# POWER.net
KiCad netlist of a schematic drawn in Altium Designer
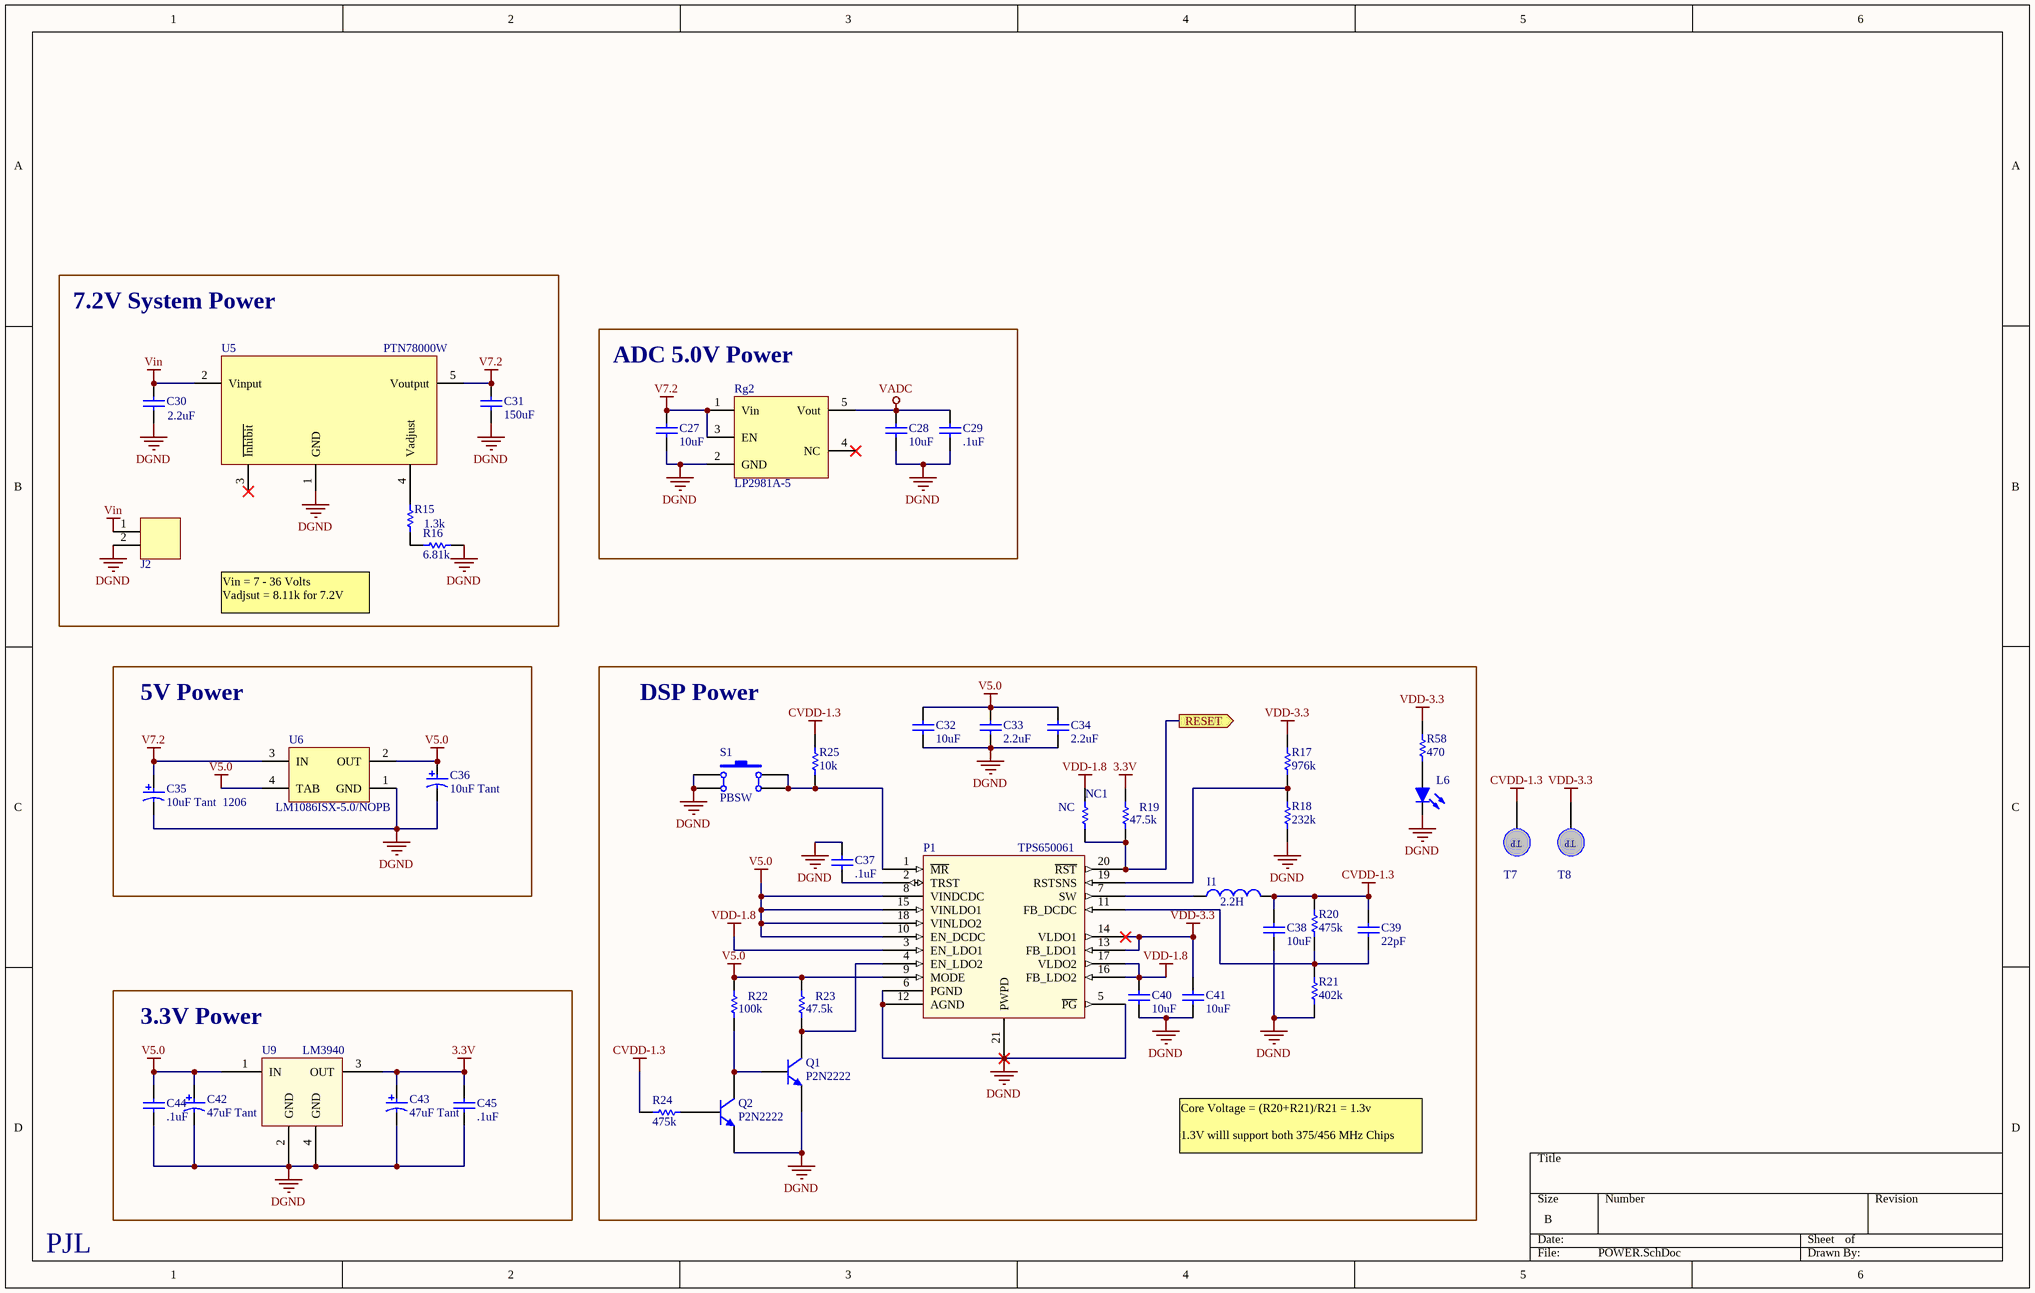
[diagram p0: POWER.SchDoc]

(export (version "E")
  (design (tool "Eeschema 10.0.6"))
  (components
    (comp (ref "C27")
      (value "10uF")
      (footprint "CAPC2012XL")
      (description "CAP CER 10UF 10V 10% X7R 0805")
      (fields
        (field (name "TOLERANCE") "±10%")
        (field (name "MANUFACTURER") "Murata Electronics North America")
      )
      (libsource (lib "SubLibrary") (part "CAP-CERAMIC-NP"))
    )
    (comp (ref "C28")
      (value "10uF")
      (footprint "CAPC2012XL")
      (description "CAP CER 10UF 10V 10% X7R 0805")
      (fields
        (field (name "TOLERANCE") "±10%")
        (field (name "MANUFACTURER") "Murata Electronics North America")
      )
      (libsource (lib "SubLibrary") (part "CAP-CERAMIC-NP"))
    )
    (comp (ref "C29")
      (value ".1uF")
      (footprint "CAPC1608XN")
      (description "CAP CER 0.1UF 10V 20% X7R 0603")
      (fields (field (name "MANUFACTURER PART NUMBER") "CX0603MRX7R6BB104") (field (name "TOLERANCE") "±20%"))
      (libsource (lib "Any") (part "CAP-CERAMIC-NP"))
    )
    (comp (ref "C30")
      (value "2.2uF")
      (footprint "CAPC2012XL")
      (description "Non Polarized Capacitor 2.2uF")
      (fields
        (field (name "MANUFACTURER") "TDK Corporation")
        (field (name "MANUFACTURER PART NUMBER") "C2012X5R1H225K")
      )
      (libsource (lib "MyLibraries") (part "Capacitor"))
    )
    (comp (ref "C31")
      (value "150uF")
      (footprint "PaulsAltiumLibrary:CAPPR2.5-6.3x11")
      (description "CAP ALUM 150UF 25V 20% RADIAL")
      (fields
        (field (name "MANUFACTURER") "Panasonic Electronic Components")
        (field (name "MANUFACTURER PART NUMBER") "EEU-FR1E151")
      )
      (libsource (lib "MyLibraries") (part "Capacitor"))
    )
    (comp (ref "C32")
      (value "10uF")
      (footprint "CAPC2012XL")
      (description "CAP CER 10UF 10V 10% X7R 0805")
      (fields
        (field (name "TOLERANCE") "±10%")
        (field (name "MANUFACTURER") "Murata Electronics North America")
      )
      (libsource (lib "SubLibrary") (part "CAP-CERAMIC-NP"))
    )
    (comp (ref "C33")
      (value "2.2uF")
      (footprint "CAPC1608XN")
      (description "CAP CER 2.2UF 10V 10% X5R 0603")
      (fields
        (field (name "TOLERANCE") "±10%")
        (field (name "MANUFACTURER") "Murata Electronics North America")
      )
      (libsource (lib "Any") (part "CAP-CERAMIC-NP"))
    )
    (comp (ref "C34")
      (value "2.2uF")
      (footprint "CAPC1608XN")
      (description "CAP CER 2.2UF 10V 10% X5R 0603")
      (fields
        (field (name "TOLERANCE") "±10%")
        (field (name "MANUFACTURER") "Murata Electronics North America")
      )
      (libsource (lib "Any") (part "CAP-CERAMIC-NP"))
    )
    (comp (ref "C35")
      (value "10uF Tant  1206")
      (footprint "CAPMP3216XN")
      (description "Capacitor, Tantalum, Polarized")
      (fields
        (field (name "MANUFACTURER") "Vishay Sprague")
        (field (name "MANUFACTURER PART NUMBER") "293D106X9016A2TE3")
      )
      (libsource (lib "Passives") (part "CAP-TANT"))
    )
    (comp (ref "C36")
      (value "10uF Tant")
      (footprint "CAPMP2012XL")
      (description "Capacitor, Tantalum, Polarized")
      (fields (field (name "MANUFACTURER") "AVX Corporation") (field (name "TOLERANCE") "±20%"))
      (libsource (lib "Passives") (part "CAP-TANT"))
    )
    (comp (ref "C37")
      (value ".1uF")
      (footprint "CAPC1608XN")
      (description "CAP CER 0.1UF 16V 10% X7R 0603")
      (fields
        (field (name "TOLERANCE") "±10%")
        (field (name "MANUFACTURER PART NUMBER") "GRM188R71C104KA01D")
      )
      (libsource (lib "Any") (part "CAP-CERAMIC-NP"))
    )
    (comp (ref "C38")
      (value "10uF")
      (footprint "CAPC2012XL")
      (description "CAP CER 10UF 10V 10% X7R 0805")
      (fields
        (field (name "TOLERANCE") "±10%")
        (field (name "MANUFACTURER") "Murata Electronics North America")
      )
      (libsource (lib "SubLibrary") (part "CAP-CERAMIC-NP"))
    )
    (comp (ref "C39")
      (value "22pF")
      (footprint "CAPC1608XN")
      (description "CAP CER 22PF 50V 5% NP0 0603")
      (fields
        (field (name "TOLERANCE") "±5%")
        (field (name "MANUFACTURER") "Murata Electronics North America")
      )
      (libsource (lib "Any") (part "CAP-CERAMIC-NP"))
    )
    (comp (ref "C40")
      (value "10uF")
      (footprint "CAPC2012XL")
      (description "CAP CER 10UF 10V 10% X7R 0805")
      (fields
        (field (name "TOLERANCE") "±10%")
        (field (name "MANUFACTURER") "Murata Electronics North America")
      )
      (libsource (lib "SubLibrary") (part "CAP-CERAMIC-NP"))
    )
    (comp (ref "C41")
      (value "10uF")
      (footprint "CAPC2012XL")
      (description "CAP CER 10UF 10V 10% X7R 0805")
      (fields
        (field (name "TOLERANCE") "±10%")
        (field (name "MANUFACTURER") "Murata Electronics North America")
      )
      (libsource (lib "SubLibrary") (part "CAP-CERAMIC-NP"))
    )
    (comp (ref "C42")
      (value "47uF Tant")
      (footprint "CAPMP2012XL")
      (description "Capacitor, Tantalum, Polarized")
      (fields
        (field (name "MANUFACTURER PART NUMBER") "TLJR476M010R3200")
        (field (name "MANUFACTURER") "AVX Corporation")
      )
      (libsource (lib "Passives") (part "CAP-TANT"))
    )
    (comp (ref "C43")
      (value "47uF Tant")
      (footprint "CAPMP2012XL")
      (description "Capacitor, Tantalum, Polarized")
      (fields
        (field (name "MANUFACTURER PART NUMBER") "TLJR476M010R3200")
        (field (name "MANUFACTURER") "AVX Corporation")
      )
      (libsource (lib "Passives") (part "CAP-TANT"))
    )
    (comp (ref "C44")
      (value ".1uF")
      (footprint "CAPC1608XN")
      (description "CAP CER 0.1UF 10V 20% X7R 0603")
      (fields (field (name "MANUFACTURER PART NUMBER") "CX0603MRX7R6BB104") (field (name "TOLERANCE") "±20%"))
      (libsource (lib "Any") (part "CAP-CERAMIC-NP"))
    )
    (comp (ref "C45")
      (value ".1uF")
      (footprint "CAPC1608XN")
      (description "CAP CER 0.1UF 10V 20% X7R 0603")
      (fields (field (name "MANUFACTURER PART NUMBER") "CX0603MRX7R6BB104") (field (name "TOLERANCE") "±20%"))
      (libsource (lib "Any") (part "CAP-CERAMIC-NP"))
    )
    (comp (ref "I1")
      (value "2.2H")
      (footprint "LPS3015")
      (fields
        (field (name "MANUFACTURER") "Coilcraft")
        (field (name "MANUFACTURER PART NUMBER") "LPS3015-222ML")
      )
      (libsource (lib "PaulsAltiumLibrary") (part "VLC5045"))
    )
    (comp (ref "J2")
      (value "2-pin Horz Sherlock")
      (footprint "MOLEX-HDR-1X2-SHERLOCK-HORZ")
      (fields
        (field (name "MANUFACTURER PART NUMBER") "0353630260")
        (field (name "MANUFACTURER") "Molex Inc")
      )
      (libsource (lib "Connectors") (part "MOLEX-HDR-1x2-SHERLOCK_RA"))
    )
    (comp (ref "L6")
      (value "LED-GREEN")
      (footprint "LED0805-GREEN")
      (description "LED GREEN CLEAR THIN 0805 SMD")
      (fields (field (name "MANUFACTURER PART NUMBER") "LTST-C171GKT"))
      (libsource (lib "Hydrophone") (part "LED-GREEN"))
    )
    (comp (ref "NC1")
      (value "NC")
      (footprint "RESC1608XN")
      (description "Resistor Chip")
      (libsource (lib "Any") (part "RES-CHIP"))
    )
    (comp (ref "P1")
      (value "TPS650061")
      (footprint "Hydrophone:QFN4-20N")
      (description "IC CONV STP-DWN 2.25MHZ DL 20QFN")
      (fields
        (field (name "MANUFACTURER") "Texas Instruments")
        (field (name "MANUFACTURER PART NUMBER") "TPS650061RUKT")
      )
      (libsource (lib "Hydrophone") (part "TPS650061"))
    )
    (comp (ref "Q1")
      (value "P2N2222")
      (footprint "PaulsAltiumLibrary:TO-92A")
      (description "TRANS GP SS NPN LP 40V TO92")
      (fields
        (field (name "MANUFACTURER PART NUMBER") "P2N2222AG")
        (field (name "MANUFACTURER") "ON Semiconductor")
      )
      (libsource (lib "Hydrophone") (part "P2N2222"))
    )
    (comp (ref "Q2")
      (value "P2N2222")
      (footprint "PaulsAltiumLibrary:TO-92A")
      (description "TRANS GP SS NPN LP 40V TO92")
      (fields
        (field (name "MANUFACTURER PART NUMBER") "P2N2222AG")
        (field (name "MANUFACTURER") "ON Semiconductor")
      )
      (libsource (lib "Hydrophone") (part "P2N2222"))
    )
    (comp (ref "R15")
      (value "1.3k")
      (footprint "RESC1608XL")
      (description "1.3k Ohm Resistor")
      (fields (field (name "TOLERANCE") "±0.5%") (field (name "MANUFACTURER PART NUMBER") "RT0603DRD071K3L"))
      (libsource (lib "MyLibraries") (part "Resistor"))
    )
    (comp (ref "R16")
      (value "6.81k")
      (footprint "RESC1608XL")
      (description "Resistor 6.81k")
      (fields (field (name "TOLERANCE") "±0.5%") (field (name "MANUFACTURER") "Yageo"))
      (libsource (lib "MyLibraries") (part "Resistor"))
    )
    (comp (ref "R17")
      (value "976k")
      (footprint "RESC1608XL")
      (description "Resistor Chip")
      (fields (field (name "MANUFACTURER PART NUMBER") "RC0603FR-07976KL") (field (name "TOLERANCE") "±1%"))
      (libsource (lib "Any") (part "RES-CHIP"))
    )
    (comp (ref "R18")
      (value "232k")
      (footprint "RESC1608XL")
      (description "Resistor Chip")
      (fields (field (name "TOLERANCE") "±1%") (field (name "MANUFACTURER PART NUMBER") "CRCW0603232KFKEA"))
      (libsource (lib "Any") (part "RES-CHIP"))
    )
    (comp (ref "R19")
      (value "47.5k")
      (footprint "RESC1608XN")
      (description "RES 47.5K OHM 1/16W 1% 0603")
      (fields (field (name "MANUFACTURER") "TE Connectivity"))
      (libsource (lib "Any") (part "RES-CHIP"))
    )
    (comp (ref "R20")
      (value "475k")
      (footprint "RESC1608XL")
      (description "Resistor Chip")
      (fields (field (name "TOLERANCE") "±1%") (field (name "MANUFACTURER") "Yageo"))
      (libsource (lib "Any") (part "RES-CHIP"))
    )
    (comp (ref "R21")
      (value "402k")
      (footprint "RESC1608XL")
      (description "RES 402K OHM 1/10W 1% 0603 SMD")
      (fields (field (name "MANUFACTURER") "Yageo") (field (name "TOLERANCE") "±1%"))
      (libsource (lib "Any") (part "RES-CHIP"))
    )
    (comp (ref "R22")
      (value "100k")
      (footprint "RESC1608XL")
      (description "RES 100K OHM 1/10W 1% 0603 SMD")
      (fields
        (field (name "MANUFACTURER PART NUMBER") "RC0603FR-07100KL")
        (field (name "MANUFACTURER") "Yageo")
      )
      (libsource (lib "Any") (part "RES-CHIP"))
    )
    (comp (ref "R23")
      (value "47.5k")
      (footprint "RESC1608XN")
      (description "RES 47.5K OHM 1/16W 1% 0603")
      (fields (field (name "MANUFACTURER") "TE Connectivity"))
      (libsource (lib "Any") (part "RES-CHIP"))
    )
    (comp (ref "R24")
      (value "475k")
      (footprint "RESC1608XL")
      (description "Resistor Chip")
      (fields (field (name "TOLERANCE") "±1%") (field (name "MANUFACTURER") "Yageo"))
      (libsource (lib "Any") (part "RES-CHIP"))
    )
    (comp (ref "R25")
      (value "10k")
      (footprint "RESC1608XL")
      (description "RES 10K OHM 1/10W 5% 0603 SMD")
      (fields (field (name "MANUFACTURER") "Yageo"))
      (libsource (lib "SubLibrary") (part "RES-CHIP"))
    )
    (comp (ref "R58")
      (value "470")
      (footprint "RESC1608XN")
      (description "RES 470 OHM .25W 5% 0603 SMD")
      (fields
        (field (name "MANUFACTURER") "Vishay Dale")
        (field (name "MANUFACTURER PART NUMBER") "CRCW0603470RJNEAHP")
      )
      (libsource (lib "SubLibrary") (part "RES-CHIP"))
    )
    (comp (ref "Rg2")
      (value "LP2981A-5")
      (footprint "TI-SOT-23_5N")
      (description "100mA 5v LDO - 0.75% accuracy")
      (fields
        (field (name "MANUFACTURER") "Texas Instruments")
        (field (name "MANUFACTURER PART NUMBER") "LP2981A-50DBVT")
      )
      (libsource (lib "SubLibrary") (part "LP2981A"))
    )
    (comp (ref "S1")
      (value "PBSW")
      (footprint "Hydrophone:PBSW")
      (description "SWITCH TACTILE SPST-NO 0.05A 12V")
      (fields
        (field (name "MANUFACTURER") "Panasonic Electronic Components")
        (field (name "PUBLISHER") "Altium Limited")
      )
      (libsource (lib "Hydrophone") (part "SW-PB"))
    )
    (comp (ref "T7")
      (value "TEST MINI")
      (footprint "TEST-POINT - 5015")
      (description "PC TEST POINT MINIATURE SMT")
      (fields
        (field (name "MANUFACTURER") "Keystone Electronics")
        (field (name "MANUFACTURER PART NUMBER") "5015")
      )
      (libsource (lib "Any") (part "TEST-POINT"))
    )
    (comp (ref "T8")
      (value "TEST MINI")
      (footprint "TEST-POINT - 5015")
      (description "PC TEST POINT MINIATURE SMT")
      (fields
        (field (name "MANUFACTURER") "Keystone Electronics")
        (field (name "MANUFACTURER PART NUMBER") "5015")
      )
      (libsource (lib "Any") (part "TEST-POINT"))
    )
    (comp (ref "U5")
      (value "PTN78000W")
      (footprint "TI-EUS - 3d")
      (description "1.5A, 7-36V Input, Variable Switching Voltage Regulator")
      (fields
        (field (name "MANUFACTURER PART NUMBER") "PTN78000WAH")
        (field (name "ORDER PART NUMBER") "296-20506-ND")
      )
      (libsource (lib "Power") (part "PTN78000W"))
    )
    (comp (ref "U6")
      (value "LM1086ISX-5.0/NOPB")
      (footprint "Hydrophone:TO263")
      (description "IC REG LDO 5V 1.5A TO-263")
      (fields (field (name "MANUFACTURER") "National Semiconductor"))
      (libsource (lib "NSC LDO") (part "LM1086ISX-5.0/NOPB"))
    )
    (comp (ref "U9")
      (value "LM3940")
      (footprint "SOT230P700X155-4N")
      (description "IC REG LDO 3.3V 1A SOT-223")
      (fields (field (name "MANUFACTURER") "National Semiconductor"))
      (libsource (lib "MyLibraries") (part "LM3940"))
    )
  )
  (nets
    (net (code "1") (name "/RESET") (class "Default")
      (node (ref "NC1") (pin "1") (pinfunction "1_1") (pintype "passive"))
      (node (ref "P1") (pin "20") (pinfunction "~{RST}_20") (pintype "output"))
      (node (ref "R19") (pin "1") (pinfunction "1_1") (pintype "passive"))
    )
    (net (code "2") (name "3.3V") (class "Default")
      (node (ref "C43") (pin "1") (pinfunction "1_1") (pintype "passive"))
      (node (ref "C45") (pin "2") (pinfunction "2_2") (pintype "passive"))
      (node (ref "R19") (pin "2") (pinfunction "2_2") (pintype "passive"))
      (node (ref "U9") (pin "3") (pinfunction "OUT_3") (pintype "power_in"))
    )
    (net (code "3") (name "CVDD-1.3") (class "Default")
      (node (ref "C38") (pin "2") (pinfunction "2_2") (pintype "passive"))
      (node (ref "C39") (pin "2") (pinfunction "2_2") (pintype "passive"))
      (node (ref "I1") (pin "2") (pinfunction "2_2") (pintype "passive"))
      (node (ref "R20") (pin "2") (pinfunction "2_2") (pintype "passive"))
      (node (ref "R24") (pin "2") (pinfunction "2_2") (pintype "passive"))
      (node (ref "R25") (pin "2") (pinfunction "2_2") (pintype "passive"))
      (node (ref "T7") (pin "1") (pinfunction "1_1") (pintype "passive"))
    )
    (net (code "4") (name "DGND") (class "Default")
      (node (ref "C27") (pin "1") (pinfunction "1_1") (pintype "passive"))
      (node (ref "C28") (pin "1") (pinfunction "1_1") (pintype "passive"))
      (node (ref "C29") (pin "1") (pinfunction "1_1") (pintype "passive"))
      (node (ref "C30") (pin "1") (pinfunction "1_1") (pintype "passive"))
      (node (ref "C31") (pin "2") (pinfunction "2_2") (pintype "passive"))
      (node (ref "C32") (pin "1") (pinfunction "1_1") (pintype "passive"))
      (node (ref "C33") (pin "1") (pinfunction "1_1") (pintype "passive"))
      (node (ref "C34") (pin "1") (pinfunction "1_1") (pintype "passive"))
      (node (ref "C35") (pin "2") (pinfunction "2_2") (pintype "passive"))
      (node (ref "C36") (pin "2") (pinfunction "2_2") (pintype "passive"))
      (node (ref "C37") (pin "2") (pinfunction "2_2") (pintype "passive"))
      (node (ref "C38") (pin "1") (pinfunction "1_1") (pintype "passive"))
      (node (ref "C40") (pin "1") (pinfunction "1_1") (pintype "passive"))
      (node (ref "C41") (pin "1") (pinfunction "1_1") (pintype "passive"))
      (node (ref "C42") (pin "2") (pinfunction "2_2") (pintype "passive"))
      (node (ref "C43") (pin "2") (pinfunction "2_2") (pintype "passive"))
      (node (ref "C44") (pin "1") (pinfunction "1_1") (pintype "passive"))
      (node (ref "C45") (pin "1") (pinfunction "1_1") (pintype "passive"))
      (node (ref "J2") (pin "2") (pinfunction "2_2") (pintype "passive"))
      (node (ref "L6") (pin "1") (pinfunction "K_1") (pintype "passive"))
      (node (ref "P1") (pin "12") (pinfunction "AGND_12") (pintype "power_in"))
      (node (ref "P1") (pin "21") (pinfunction "PWPD_21") (pintype "power_in"))
      (node (ref "P1") (pin "5") (pinfunction "~{PG}_5") (pintype "output"))
      (node (ref "P1") (pin "6") (pinfunction "PGND_6") (pintype "power_in"))
      (node (ref "Q1") (pin "3") (pinfunction "E_3") (pintype "passive"))
      (node (ref "Q2") (pin "3") (pinfunction "E_3") (pintype "passive"))
      (node (ref "R16") (pin "1") (pinfunction "1_1") (pintype "passive"))
      (node (ref "R18") (pin "2") (pinfunction "2_2") (pintype "passive"))
      (node (ref "R21") (pin "2") (pinfunction "2_2") (pintype "passive"))
      (node (ref "Rg2") (pin "2") (pinfunction "GND_2") (pintype "power_in"))
      (node (ref "S1") (pin "1") (pinfunction "A_1") (pintype "passive"))
      (node (ref "S1") (pin "2") (pinfunction "A'_2") (pintype "passive"))
      (node (ref "U5") (pin "1") (pinfunction "GND_1") (pintype "passive"))
      (node (ref "U6") (pin "1") (pinfunction "GND_1") (pintype "power_in"))
      (node (ref "U9") (pin "2") (pinfunction "GND_2") (pintype "power_in"))
      (node (ref "U9") (pin "4") (pinfunction "GND_4") (pintype "power_in"))
    )
    (net (code "5") (name "Net-(L6-A)") (class "Default")
      (node (ref "L6") (pin "2") (pinfunction "A_2") (pintype "passive"))
      (node (ref "R58") (pin "1") (pinfunction "1_1") (pintype "passive"))
    )
    (net (code "6") (name "Net-(P1-EN_LDO2)") (class "Default")
      (node (ref "P1") (pin "4") (pinfunction "EN_LDO2_4") (pintype "input"))
      (node (ref "Q1") (pin "1") (pinfunction "C_1") (pintype "passive"))
      (node (ref "R23") (pin "1") (pinfunction "1_1") (pintype "passive"))
    )
    (net (code "7") (name "Net-(P1-FB_DCDC)") (class "Default")
      (node (ref "C39") (pin "1") (pinfunction "1_1") (pintype "passive"))
      (node (ref "P1") (pin "11") (pinfunction "FB_DCDC_11") (pintype "input"))
      (node (ref "R20") (pin "1") (pinfunction "1_1") (pintype "passive"))
      (node (ref "R21") (pin "1") (pinfunction "1_1") (pintype "passive"))
    )
    (net (code "8") (name "Net-(P1-RSTSNS)") (class "Default")
      (node (ref "P1") (pin "19") (pinfunction "RSTSNS_19") (pintype "input"))
      (node (ref "R17") (pin "2") (pinfunction "2_2") (pintype "passive"))
      (node (ref "R18") (pin "1") (pinfunction "1_1") (pintype "passive"))
    )
    (net (code "9") (name "Net-(P1-SW)") (class "Default")
      (node (ref "I1") (pin "1") (pinfunction "1_1") (pintype "passive"))
      (node (ref "P1") (pin "7") (pinfunction "SW_7") (pintype "output"))
    )
    (net (code "10") (name "Net-(P1-TRST)") (class "Default")
      (node (ref "C37") (pin "1") (pinfunction "1_1") (pintype "passive"))
      (node (ref "P1") (pin "2") (pinfunction "TRST_2") (pintype "bidirectional"))
    )
    (net (code "11") (name "Net-(P1-~{MR})") (class "Default")
      (node (ref "P1") (pin "1") (pinfunction "~{MR}_1") (pintype "input"))
      (node (ref "R25") (pin "1") (pinfunction "1_1") (pintype "passive"))
      (node (ref "S1") (pin "3") (pinfunction "B_3") (pintype "passive"))
      (node (ref "S1") (pin "4") (pinfunction "B'_4") (pintype "passive"))
    )
    (net (code "12") (name "Net-(Q1-B)") (class "Default")
      (node (ref "Q1") (pin "2") (pinfunction "B_2") (pintype "passive"))
      (node (ref "Q2") (pin "1") (pinfunction "C_1") (pintype "passive"))
      (node (ref "R22") (pin "1") (pinfunction "1_1") (pintype "passive"))
    )
    (net (code "13") (name "Net-(Q2-B)") (class "Default")
      (node (ref "Q2") (pin "2") (pinfunction "B_2") (pintype "passive"))
      (node (ref "R24") (pin "1") (pinfunction "1_1") (pintype "passive"))
    )
    (net (code "14") (name "Net-(R15-Pad2)") (class "Default")
      (node (ref "R15") (pin "2") (pinfunction "2_2") (pintype "passive"))
      (node (ref "R16") (pin "2") (pinfunction "2_2") (pintype "passive"))
    )
    (net (code "15") (name "Net-(U5-Vadjust)") (class "Default")
      (node (ref "R15") (pin "1") (pinfunction "1_1") (pintype "passive"))
      (node (ref "U5") (pin "4") (pinfunction "Vadjust_4") (pintype "passive"))
    )
    (net (code "16") (name "V5.0") (class "Default")
      (node (ref "C32") (pin "2") (pinfunction "2_2") (pintype "passive"))
      (node (ref "C33") (pin "2") (pinfunction "2_2") (pintype "passive"))
      (node (ref "C34") (pin "2") (pinfunction "2_2") (pintype "passive"))
      (node (ref "C36") (pin "1") (pinfunction "1_1") (pintype "passive"))
      (node (ref "C42") (pin "1") (pinfunction "1_1") (pintype "passive"))
      (node (ref "C44") (pin "2") (pinfunction "2_2") (pintype "passive"))
      (node (ref "P1") (pin "10") (pinfunction "EN_DCDC_10") (pintype "input"))
      (node (ref "P1") (pin "15") (pinfunction "VINLDO1_15") (pintype "input"))
      (node (ref "P1") (pin "18") (pinfunction "VINLDO2_18") (pintype "input"))
      (node (ref "P1") (pin "8") (pinfunction "VINDCDC_8") (pintype "power_in"))
      (node (ref "P1") (pin "9") (pinfunction "MODE_9") (pintype "input"))
      (node (ref "R22") (pin "2") (pinfunction "2_2") (pintype "passive"))
      (node (ref "R23") (pin "2") (pinfunction "2_2") (pintype "passive"))
      (node (ref "U6") (pin "2") (pinfunction "OUT_2") (pintype "power_in"))
      (node (ref "U6") (pin "4") (pinfunction "TAB_4") (pintype "power_in"))
      (node (ref "U9") (pin "1") (pinfunction "IN_1") (pintype "power_in"))
    )
    (net (code "17") (name "V7.2") (class "Default")
      (node (ref "C27") (pin "2") (pinfunction "2_2") (pintype "passive"))
      (node (ref "C31") (pin "1") (pinfunction "1_1") (pintype "passive"))
      (node (ref "C35") (pin "1") (pinfunction "1_1") (pintype "passive"))
      (node (ref "Rg2") (pin "1") (pinfunction "Vin_1") (pintype "power_in"))
      (node (ref "Rg2") (pin "3") (pinfunction "EN_3") (pintype "passive"))
      (node (ref "U5") (pin "5") (pinfunction "Voutput_5") (pintype "passive"))
      (node (ref "U6") (pin "3") (pinfunction "IN_3") (pintype "power_in"))
    )
    (net (code "18") (name "VADC") (class "Default")
      (node (ref "C28") (pin "2") (pinfunction "2_2") (pintype "passive"))
      (node (ref "C29") (pin "2") (pinfunction "2_2") (pintype "passive"))
      (node (ref "Rg2") (pin "5") (pinfunction "Vout_5") (pintype "power_in"))
    )
    (net (code "19") (name "VDD-1.8") (class "Default")
      (node (ref "C40") (pin "2") (pinfunction "2_2") (pintype "passive"))
      (node (ref "NC1") (pin "2") (pinfunction "2_2") (pintype "passive"))
      (node (ref "P1") (pin "16") (pinfunction "FB_LDO2_16") (pintype "input"))
      (node (ref "P1") (pin "17") (pinfunction "VLDO2_17") (pintype "output"))
      (node (ref "P1") (pin "3") (pinfunction "EN_LDO1_3") (pintype "input"))
    )
    (net (code "20") (name "VDD-3.3") (class "Default")
      (node (ref "C41") (pin "2") (pinfunction "2_2") (pintype "passive"))
      (node (ref "P1") (pin "13") (pinfunction "FB_LDO1_13") (pintype "input"))
      (node (ref "P1") (pin "14") (pinfunction "VLDO1_14") (pintype "output"))
      (node (ref "R17") (pin "1") (pinfunction "1_1") (pintype "passive"))
      (node (ref "R58") (pin "2") (pinfunction "2_2") (pintype "passive"))
      (node (ref "T8") (pin "1") (pinfunction "1_1") (pintype "passive"))
    )
    (net (code "21") (name "Vin") (class "Default")
      (node (ref "C30") (pin "2") (pinfunction "2_2") (pintype "passive"))
      (node (ref "J2") (pin "1") (pinfunction "1_1") (pintype "passive"))
      (node (ref "U5") (pin "2") (pinfunction "Vinput_2") (pintype "passive"))
    )
    (net (code "22") (name "unconnected-(Rg2-NC-Pad4)") (class "Default")
      (node (ref "Rg2") (pin "4") (pinfunction "NC_4") (pintype "passive+no_connect"))
    )
    (net (code "23") (name "unconnected-(U5-~{Inhibit}-Pad3)") (class "Default")
      (node (ref "U5") (pin "3") (pinfunction "~{Inhibit}_3") (pintype "passive+no_connect"))
    )
  )
)
